# STM32F405RGT6.net
KiCad netlist of a schematic drawn in Altium Designer
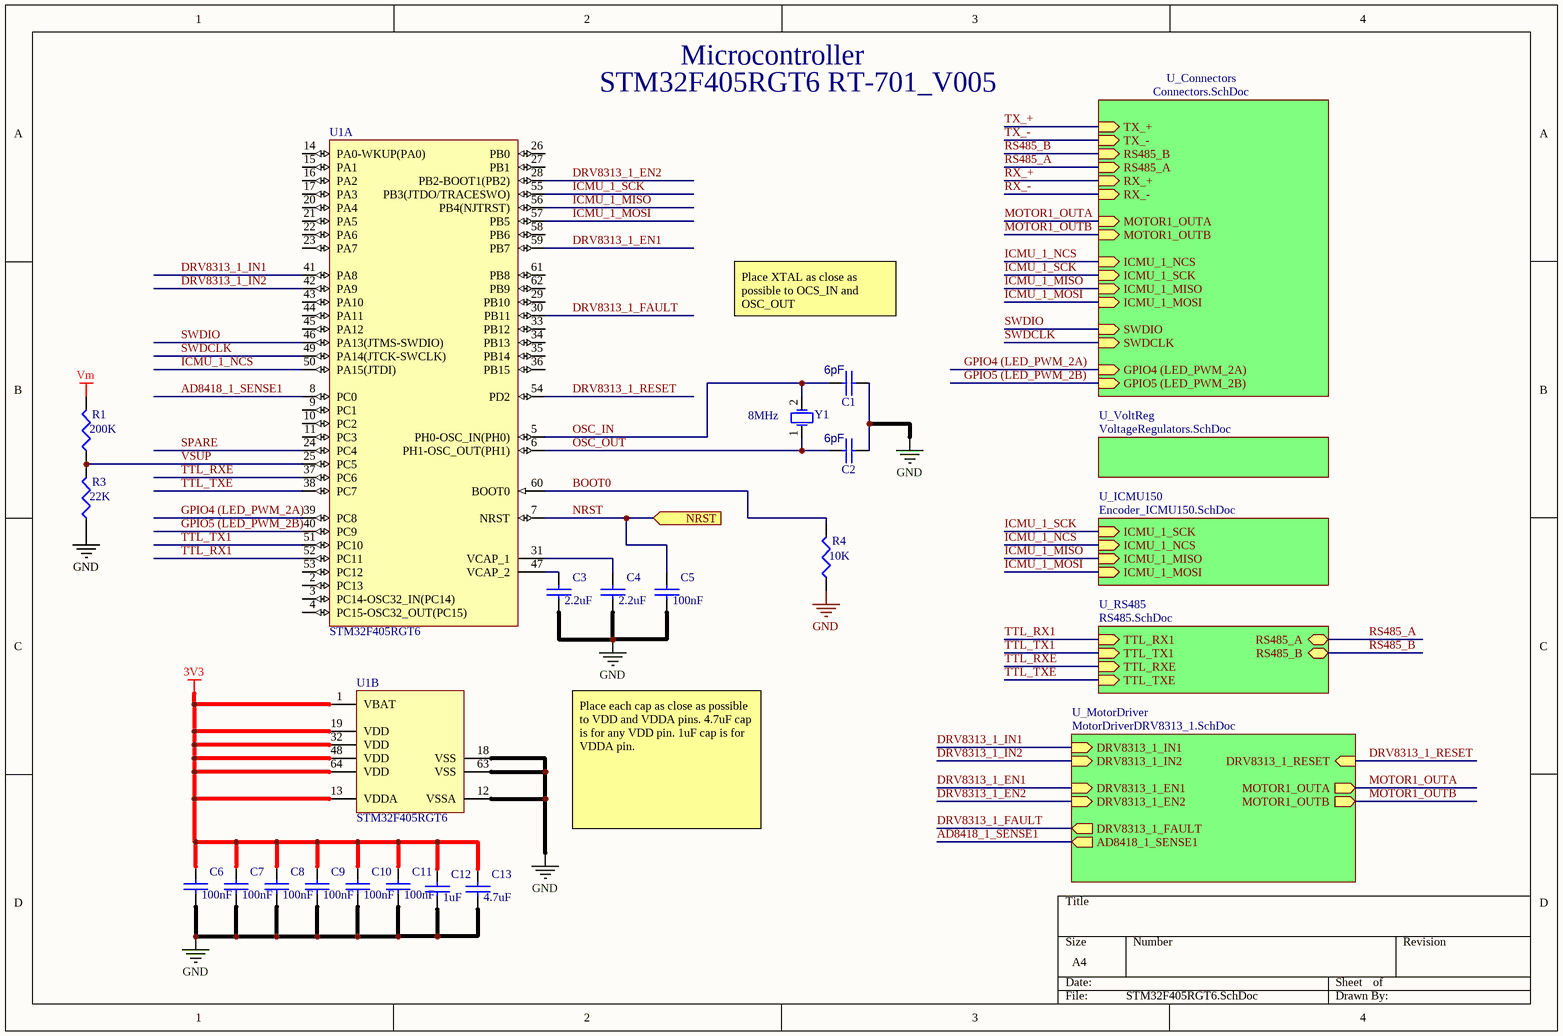
[diagram p0: STM32F405RGT6.SchDoc]

(export (version "E")
  (design (tool "Eeschema 10.0.6"))
  (components
    (comp (ref "C1")
      (value "Capacitor")
      (footprint "CAP0402")
      (description "CAP CER 6PF 100V C0G/NP0 0402")
      (fields (field (name "CAPACITANCE") "6pF"))
      (libsource (lib "") (part "Capacitor_1"))
    )
    (comp (ref "C2")
      (value "Capacitor")
      (footprint "CAP0402")
      (description "CAP CER 6PF 100V C0G/NP0 0402")
      (fields (field (name "CAPACITANCE") "6pF"))
      (libsource (lib "") (part "Capacitor_1"))
    )
    (comp (ref "C3")
      (value "2.2uF")
      (footprint "CAP0402")
      (description "Capacitor")
      (fields
        (field (name "MANUFACTURER") "TDK Corporation")
        (field (name "MANUFACTURER PART NUMBER") "C1005X5R0J225K050BC")
      )
      (libsource (lib "BPL-ShematicLibrary") (part "Capacitor"))
    )
    (comp (ref "C4")
      (value "2.2uF")
      (footprint "CAP0402")
      (description "Capacitor")
      (fields
        (field (name "MANUFACTURER") "TDK Corporation")
        (field (name "MANUFACTURER PART NUMBER") "C1005X5R0J225K050BC")
      )
      (libsource (lib "BPL-ShematicLibrary") (part "Capacitor"))
    )
    (comp (ref "C5")
      (value "100nF")
      (footprint "CAP0402")
      (description "Capacitor")
      (fields
        (field (name "MANUFACTURER") "TDK Corporation")
        (field (name "MANUFACTURER PART NUMBER") "CGA2B3X7R1V104K050BB")
      )
      (libsource (lib "BPL-ShematicLibrary") (part "Capacitor"))
    )
    (comp (ref "C6")
      (value "100nF")
      (footprint "CAP0402")
      (description "Capacitor")
      (fields
        (field (name "MANUFACTURER") "TDK Corporation")
        (field (name "MANUFACTURER PART NUMBER") "CGA2B3X7R1V104K050BB")
      )
      (libsource (lib "BPL-ShematicLibrary") (part "Capacitor"))
    )
    (comp (ref "C7")
      (value "100nF")
      (footprint "CAP0402")
      (description "Capacitor")
      (fields
        (field (name "MANUFACTURER") "TDK Corporation")
        (field (name "MANUFACTURER PART NUMBER") "CGA2B3X7R1V104K050BB")
      )
      (libsource (lib "BPL-ShematicLibrary") (part "Capacitor"))
    )
    (comp (ref "C8")
      (value "100nF")
      (footprint "CAP0402")
      (description "Capacitor")
      (fields
        (field (name "MANUFACTURER") "TDK Corporation")
        (field (name "MANUFACTURER PART NUMBER") "CGA2B3X7R1V104K050BB")
      )
      (libsource (lib "BPL-ShematicLibrary") (part "Capacitor"))
    )
    (comp (ref "C9")
      (value "100nF")
      (footprint "CAP0402")
      (description "Capacitor")
      (fields
        (field (name "MANUFACTURER") "TDK Corporation")
        (field (name "MANUFACTURER PART NUMBER") "CGA2B3X7R1V104K050BB")
      )
      (libsource (lib "BPL-ShematicLibrary") (part "Capacitor"))
    )
    (comp (ref "C10")
      (value "100nF")
      (footprint "CAP0402")
      (description "Capacitor")
      (fields
        (field (name "MANUFACTURER") "TDK Corporation")
        (field (name "MANUFACTURER PART NUMBER") "CGA2B3X7R1V104K050BB")
      )
      (libsource (lib "BPL-ShematicLibrary") (part "Capacitor"))
    )
    (comp (ref "C11")
      (value "100nF")
      (footprint "CAP0402")
      (description "Capacitor")
      (fields
        (field (name "MANUFACTURER") "TDK Corporation")
        (field (name "MANUFACTURER PART NUMBER") "CGA2B3X7R1V104K050BB")
      )
      (libsource (lib "BPL-ShematicLibrary") (part "Capacitor"))
    )
    (comp (ref "C12")
      (value "1uF")
      (footprint "CAP0402")
      (description "Capacitor")
      (fields
        (field (name "MANUFACTURER") "TDK Corporation")
        (field (name "MANUFACTURER PART NUMBER") "C1005X5R1V105K050BC")
      )
      (libsource (lib "BPL-ShematicLibrary") (part "Capacitor"))
    )
    (comp (ref "C13")
      (value "4.7uF")
      (footprint "CAP0402")
      (description "Capacitor")
      (fields
        (field (name "MANUFACTURER") "TDK Corporation")
        (field (name "MANUFACTURER PART NUMBER") "C1005X5R0J475K050BC")
      )
      (libsource (lib "BPL-ShematicLibrary") (part "Capacitor"))
    )
    (comp (ref "R1")
      (value "200K")
      (footprint "RES0402")
      (description "Resistor")
      (fields
        (field (name "MANUFACTURER") "Yageo")
        (field (name "MANUFACTURER PART NUMBER") "RC0402FR-07200KL")
      )
      (libsource (lib "BPL-ShematicLibrary") (part "Resistor"))
    )
    (comp (ref "R3")
      (value "22K")
      (footprint "RES0402")
      (description "Resistor")
      (fields
        (field (name "MANUFACTURER") "Yageo")
        (field (name "MANUFACTURER PART NUMBER") "RC0402FR-0722KL")
      )
      (libsource (lib "BPL-ShematicLibrary") (part "Resistor"))
    )
    (comp (ref "R4")
      (value "10K")
      (footprint "RES0402")
      (description "Resistor")
      (fields
        (field (name "MANUFACTURER") "Yageo")
        (field (name "MANUFACTURER PART NUMBER") "RC0402FR-0710KL")
      )
      (libsource (lib "BPL-ShematicLibrary") (part "Resistor"))
    )
    (comp (ref "U1")
      (value "STM32F405RGT6")
      (footprint "STM-LQFP64_N")
      (fields (field (name "MANUFACTURER") "STMicroelectronics"))
      (libsource (lib "BPL-ShematicLibrary") (part "STM32F405RGT6"))
    )
    (comp (ref "Y1")
      (value "8MHz")
      (footprint "2-SMD-XTAL (3.2x2.5)")
      (description "Crystal Oscillator")
      (fields
        (field (name "MANUFACTURER") "NDK")
        (field (name "MANUFACTURER PART NUMBER") "NX3225GD-8MHZ-STD-CRA-3")
      )
      (libsource (lib "BPL-ShematicLibrary") (part "Crystal Oscillator"))
    )
  )
  (nets
    (net (code "1") (name "/AD8418_1_SENSE1") (class "Default")
      (node (ref "U1") (pin "8") (pinfunction "PC0_8") (pintype "bidirectional"))
    )
    (net (code "2") (name "/BOOT0") (class "Default")
      (node (ref "R4") (pin "2") (pinfunction "2_2") (pintype "passive"))
      (node (ref "U1") (pin "60") (pinfunction "BOOT0_60") (pintype "input"))
    )
    (net (code "3") (name "/DRV8313_1_EN1") (class "Default")
      (node (ref "U1") (pin "59") (pinfunction "PB7_59") (pintype "bidirectional"))
    )
    (net (code "4") (name "/DRV8313_1_EN2") (class "Default")
      (node (ref "U1") (pin "28") (pinfunction "PB2-BOOT1(PB2)_28") (pintype "bidirectional"))
    )
    (net (code "5") (name "/DRV8313_1_FAULT") (class "Default")
      (node (ref "U1") (pin "30") (pinfunction "PB11_30") (pintype "bidirectional"))
    )
    (net (code "6") (name "/DRV8313_1_IN1") (class "Default")
      (node (ref "U1") (pin "41") (pinfunction "PA8_41") (pintype "bidirectional"))
    )
    (net (code "7") (name "/DRV8313_1_IN2") (class "Default")
      (node (ref "U1") (pin "42") (pinfunction "PA9_42") (pintype "bidirectional"))
    )
    (net (code "8") (name "/DRV8313_1_RESET") (class "Default")
      (node (ref "U1") (pin "54") (pinfunction "PD2_54") (pintype "bidirectional"))
    )
    (net (code "9") (name "/GPIO4 (LED_PWM_2A)") (class "Default")
      (node (ref "U1") (pin "39") (pinfunction "PC8_39") (pintype "bidirectional"))
    )
    (net (code "10") (name "/GPIO5 (LED_PWM_2B)") (class "Default")
      (node (ref "U1") (pin "40") (pinfunction "PC9_40") (pintype "bidirectional"))
    )
    (net (code "11") (name "/ICMU_1_MISO") (class "Default")
      (node (ref "U1") (pin "56") (pinfunction "PB4(NJTRST)_56") (pintype "bidirectional"))
    )
    (net (code "12") (name "/ICMU_1_MOSI") (class "Default")
      (node (ref "U1") (pin "57") (pinfunction "PB5_57") (pintype "bidirectional"))
    )
    (net (code "13") (name "/ICMU_1_NCS") (class "Default")
      (node (ref "U1") (pin "50") (pinfunction "PA15(JTDI)_50") (pintype "bidirectional"))
    )
    (net (code "14") (name "/ICMU_1_SCK") (class "Default")
      (node (ref "U1") (pin "55") (pinfunction "PB3(JTDO/TRACESWO)_55") (pintype "bidirectional"))
    )
    (net (code "17") (name "/NRST") (class "Default")
      (node (ref "C5") (pin "1") (pinfunction "1_1") (pintype "passive"))
      (node (ref "U1") (pin "7") (pinfunction "NRST_7") (pintype "bidirectional"))
    )
    (net (code "18") (name "/OSC_IN") (class "Default")
      (node (ref "C1") (pin "2") (pinfunction "2_2") (pintype "passive"))
      (node (ref "U1") (pin "5") (pinfunction "PH0-OSC_IN(PH0)_5") (pintype "bidirectional"))
      (node (ref "Y1") (pin "2") (pinfunction "2_2") (pintype "passive"))
    )
    (net (code "19") (name "/OSC_OUT") (class "Default")
      (node (ref "C2") (pin "2") (pinfunction "2_2") (pintype "passive"))
      (node (ref "U1") (pin "6") (pinfunction "PH1-OSC_OUT(PH1)_6") (pintype "bidirectional"))
      (node (ref "Y1") (pin "1") (pinfunction "1_1") (pintype "passive"))
    )
    (net (code "24") (name "/SPARE") (class "Default")
      (node (ref "U1") (pin "24") (pinfunction "PC4_24") (pintype "bidirectional"))
    )
    (net (code "25") (name "/SWDCLK") (class "Default")
      (node (ref "U1") (pin "49") (pinfunction "PA14(JTCK-SWCLK)_49") (pintype "bidirectional"))
    )
    (net (code "26") (name "/SWDIO") (class "Default")
      (node (ref "U1") (pin "46") (pinfunction "PA13(JTMS-SWDIO)_46") (pintype "bidirectional"))
    )
    (net (code "27") (name "/TTL_RX1") (class "Default")
      (node (ref "U1") (pin "52") (pinfunction "PC11_52") (pintype "bidirectional"))
    )
    (net (code "28") (name "/TTL_RXE") (class "Default")
      (node (ref "U1") (pin "37") (pinfunction "PC6_37") (pintype "bidirectional"))
    )
    (net (code "29") (name "/TTL_TX1") (class "Default")
      (node (ref "U1") (pin "51") (pinfunction "PC10_51") (pintype "bidirectional"))
    )
    (net (code "30") (name "/TTL_TXE") (class "Default")
      (node (ref "U1") (pin "38") (pinfunction "PC7_38") (pintype "bidirectional"))
    )
    (net (code "33") (name "/VSUP") (class "Default")
      (node (ref "R1") (pin "1") (pinfunction "1_1") (pintype "passive"))
      (node (ref "R3") (pin "2") (pinfunction "2_2") (pintype "passive"))
      (node (ref "U1") (pin "25") (pinfunction "PC5_25") (pintype "bidirectional"))
    )
    (net (code "34") (name "3V3") (class "Default")
      (node (ref "C10") (pin "1") (pinfunction "1_1") (pintype "passive"))
      (node (ref "C11") (pin "1") (pinfunction "1_1") (pintype "passive"))
      (node (ref "C12") (pin "1") (pinfunction "1_1") (pintype "passive"))
      (node (ref "C13") (pin "1") (pinfunction "1_1") (pintype "passive"))
      (node (ref "C6") (pin "1") (pinfunction "1_1") (pintype "passive"))
      (node (ref "C7") (pin "1") (pinfunction "1_1") (pintype "passive"))
      (node (ref "C8") (pin "1") (pinfunction "1_1") (pintype "passive"))
      (node (ref "C9") (pin "1") (pinfunction "1_1") (pintype "passive"))
      (node (ref "U1") (pin "1") (pinfunction "VBAT_1") (pintype "power_in"))
      (node (ref "U1") (pin "13") (pinfunction "VDDA_13") (pintype "power_in"))
      (node (ref "U1") (pin "19") (pinfunction "VDD_19") (pintype "power_in"))
      (node (ref "U1") (pin "32") (pinfunction "VDD_32") (pintype "power_in"))
      (node (ref "U1") (pin "48") (pinfunction "VDD_48") (pintype "power_in"))
      (node (ref "U1") (pin "64") (pinfunction "VDD_64") (pintype "power_in"))
    )
    (net (code "35") (name "GND") (class "Default")
      (node (ref "C1") (pin "1") (pinfunction "1_1") (pintype "passive"))
      (node (ref "C10") (pin "2") (pinfunction "2_2") (pintype "passive"))
      (node (ref "C11") (pin "2") (pinfunction "2_2") (pintype "passive"))
      (node (ref "C12") (pin "2") (pinfunction "2_2") (pintype "passive"))
      (node (ref "C13") (pin "2") (pinfunction "2_2") (pintype "passive"))
      (node (ref "C2") (pin "1") (pinfunction "1_1") (pintype "passive"))
      (node (ref "C3") (pin "2") (pinfunction "2_2") (pintype "passive"))
      (node (ref "C4") (pin "2") (pinfunction "2_2") (pintype "passive"))
      (node (ref "C5") (pin "2") (pinfunction "2_2") (pintype "passive"))
      (node (ref "C6") (pin "2") (pinfunction "2_2") (pintype "passive"))
      (node (ref "C7") (pin "2") (pinfunction "2_2") (pintype "passive"))
      (node (ref "C8") (pin "2") (pinfunction "2_2") (pintype "passive"))
      (node (ref "C9") (pin "2") (pinfunction "2_2") (pintype "passive"))
      (node (ref "R3") (pin "1") (pinfunction "1_1") (pintype "passive"))
      (node (ref "R4") (pin "1") (pinfunction "1_1") (pintype "passive"))
      (node (ref "U1") (pin "12") (pinfunction "VSSA_12") (pintype "power_in"))
      (node (ref "U1") (pin "18") (pinfunction "VSS_18") (pintype "power_in"))
      (node (ref "U1") (pin "63") (pinfunction "VSS_63") (pintype "power_in"))
    )
    (net (code "36") (name "Net-(U1A-VCAP_1)") (class "Default")
      (node (ref "C4") (pin "1") (pinfunction "1_1") (pintype "passive"))
      (node (ref "U1") (pin "31") (pinfunction "VCAP_1_31") (pintype "power_in"))
    )
    (net (code "37") (name "Net-(U1A-VCAP_2)") (class "Default")
      (node (ref "C3") (pin "1") (pinfunction "1_1") (pintype "passive"))
      (node (ref "U1") (pin "47") (pinfunction "VCAP_2_47") (pintype "power_in"))
    )
    (net (code "38") (name "Vm") (class "Default")
      (node (ref "R1") (pin "2") (pinfunction "2_2") (pintype "passive"))
    )
    (net (code "39") (name "unconnected-(U1A-PA0-WKUP(PA0)-Pad14)") (class "Default")
      (node (ref "U1") (pin "14") (pinfunction "PA0-WKUP(PA0)_14") (pintype "bidirectional"))
    )
    (net (code "40") (name "unconnected-(U1A-PA1-Pad15)") (class "Default")
      (node (ref "U1") (pin "15") (pinfunction "PA1_15") (pintype "bidirectional"))
    )
    (net (code "41") (name "unconnected-(U1A-PA2-Pad16)") (class "Default")
      (node (ref "U1") (pin "16") (pinfunction "PA2_16") (pintype "bidirectional"))
    )
    (net (code "42") (name "unconnected-(U1A-PA3-Pad17)") (class "Default")
      (node (ref "U1") (pin "17") (pinfunction "PA3_17") (pintype "bidirectional"))
    )
    (net (code "43") (name "unconnected-(U1A-PA4-Pad20)") (class "Default")
      (node (ref "U1") (pin "20") (pinfunction "PA4_20") (pintype "bidirectional"))
    )
    (net (code "44") (name "unconnected-(U1A-PA5-Pad21)") (class "Default")
      (node (ref "U1") (pin "21") (pinfunction "PA5_21") (pintype "bidirectional"))
    )
    (net (code "45") (name "unconnected-(U1A-PA6-Pad22)") (class "Default")
      (node (ref "U1") (pin "22") (pinfunction "PA6_22") (pintype "bidirectional"))
    )
    (net (code "46") (name "unconnected-(U1A-PA7-Pad23)") (class "Default")
      (node (ref "U1") (pin "23") (pinfunction "PA7_23") (pintype "bidirectional"))
    )
    (net (code "47") (name "unconnected-(U1A-PA10-Pad43)") (class "Default")
      (node (ref "U1") (pin "43") (pinfunction "PA10_43") (pintype "bidirectional"))
    )
    (net (code "48") (name "unconnected-(U1A-PA11-Pad44)") (class "Default")
      (node (ref "U1") (pin "44") (pinfunction "PA11_44") (pintype "bidirectional"))
    )
    (net (code "49") (name "unconnected-(U1A-PA12-Pad45)") (class "Default")
      (node (ref "U1") (pin "45") (pinfunction "PA12_45") (pintype "bidirectional"))
    )
    (net (code "50") (name "unconnected-(U1A-PB0-Pad26)") (class "Default")
      (node (ref "U1") (pin "26") (pinfunction "PB0_26") (pintype "bidirectional"))
    )
    (net (code "51") (name "unconnected-(U1A-PB1-Pad27)") (class "Default")
      (node (ref "U1") (pin "27") (pinfunction "PB1_27") (pintype "bidirectional"))
    )
    (net (code "52") (name "unconnected-(U1A-PB6-Pad58)") (class "Default")
      (node (ref "U1") (pin "58") (pinfunction "PB6_58") (pintype "bidirectional"))
    )
    (net (code "53") (name "unconnected-(U1A-PB8-Pad61)") (class "Default")
      (node (ref "U1") (pin "61") (pinfunction "PB8_61") (pintype "bidirectional"))
    )
    (net (code "54") (name "unconnected-(U1A-PB9-Pad62)") (class "Default")
      (node (ref "U1") (pin "62") (pinfunction "PB9_62") (pintype "bidirectional"))
    )
    (net (code "55") (name "unconnected-(U1A-PB10-Pad29)") (class "Default")
      (node (ref "U1") (pin "29") (pinfunction "PB10_29") (pintype "bidirectional"))
    )
    (net (code "56") (name "unconnected-(U1A-PB12-Pad33)") (class "Default")
      (node (ref "U1") (pin "33") (pinfunction "PB12_33") (pintype "bidirectional"))
    )
    (net (code "57") (name "unconnected-(U1A-PB13-Pad34)") (class "Default")
      (node (ref "U1") (pin "34") (pinfunction "PB13_34") (pintype "bidirectional"))
    )
    (net (code "58") (name "unconnected-(U1A-PB14-Pad35)") (class "Default")
      (node (ref "U1") (pin "35") (pinfunction "PB14_35") (pintype "bidirectional"))
    )
    (net (code "59") (name "unconnected-(U1A-PB15-Pad36)") (class "Default")
      (node (ref "U1") (pin "36") (pinfunction "PB15_36") (pintype "bidirectional"))
    )
    (net (code "60") (name "unconnected-(U1A-PC1-Pad9)") (class "Default")
      (node (ref "U1") (pin "9") (pinfunction "PC1_9") (pintype "bidirectional"))
    )
    (net (code "61") (name "unconnected-(U1A-PC2-Pad10)") (class "Default")
      (node (ref "U1") (pin "10") (pinfunction "PC2_10") (pintype "bidirectional"))
    )
    (net (code "62") (name "unconnected-(U1A-PC3-Pad11)") (class "Default")
      (node (ref "U1") (pin "11") (pinfunction "PC3_11") (pintype "bidirectional"))
    )
    (net (code "63") (name "unconnected-(U1A-PC12-Pad53)") (class "Default")
      (node (ref "U1") (pin "53") (pinfunction "PC12_53") (pintype "bidirectional"))
    )
    (net (code "64") (name "unconnected-(U1A-PC13-Pad2)") (class "Default")
      (node (ref "U1") (pin "2") (pinfunction "PC13_2") (pintype "bidirectional"))
    )
    (net (code "65") (name "unconnected-(U1A-PC14-OSC32_IN(PC14)-Pad3)") (class "Default")
      (node (ref "U1") (pin "3") (pinfunction "PC14-OSC32_IN(PC14)_3") (pintype "bidirectional"))
    )
    (net (code "66") (name "unconnected-(U1A-PC15-OSC32_OUT(PC15)-Pad4)") (class "Default")
      (node (ref "U1") (pin "4") (pinfunction "PC15-OSC32_OUT(PC15)_4") (pintype "bidirectional"))
    )
  )
)
